# B293B_PIC32.net
KiCad netlist of a schematic drawn in Altium Designer
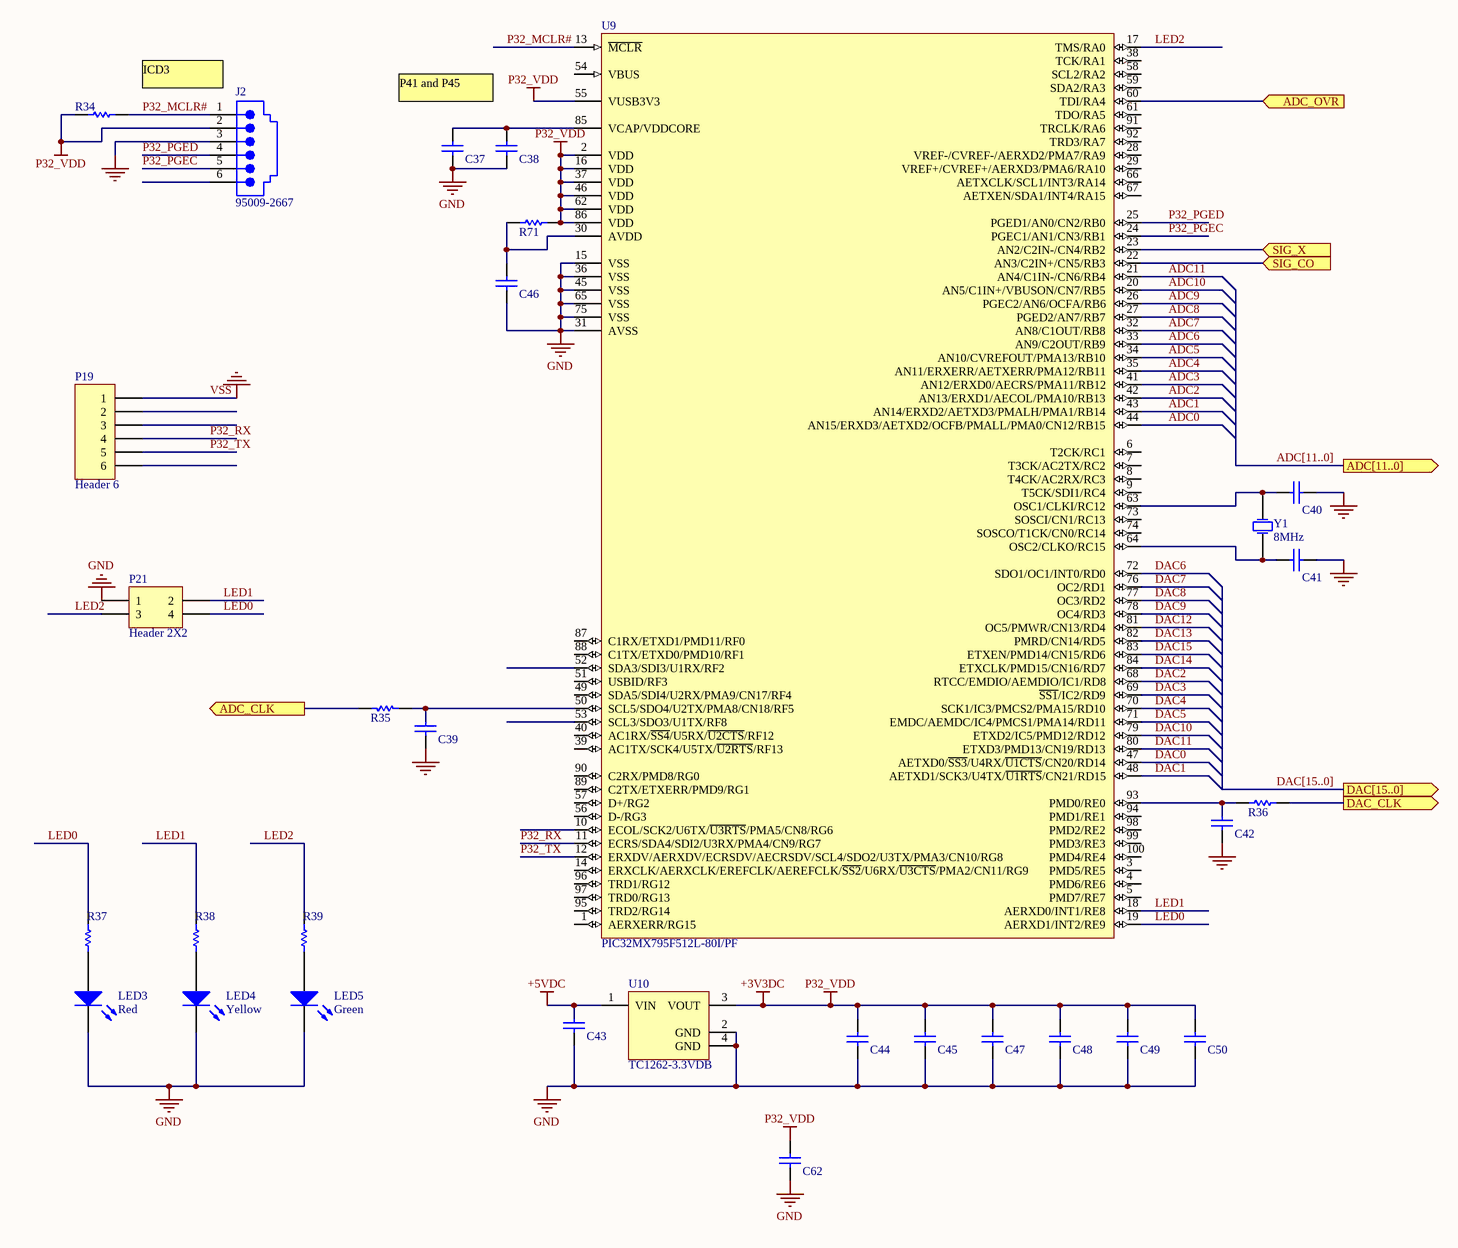
[diagram p0: B293B PIC32.SchDoc]

(export (version "E")
  (design (tool "Eeschema 10.0.6"))
  (components
    (comp (ref "C37")
      (value "CAP 10uF 25V 0805(2012)")
      (footprint "CAPC0805(2012)145_N")
      (description "CAP 10uF 25V ±20% 0805 (2012 Metric) Thickness 1.45mm SMD")
      (fields (field (name "TOLERANCE") "±20%"))
      (libsource (lib "Altium Content Vault") (part "CAP"))
    )
    (comp (ref "C38")
      (value "CAP 100nF 50V 1206(3216)")
      (footprint "CAPC1206(3216)170_L")
      (description "CAP 100nF 50V ±10% 1206 (3216 Metric) Thickness 1.7mm SMD")
      (fields (field (name "TOLERANCE") "±10%"))
      (libsource (lib "Altium Content Vault") (part "CAP"))
    )
    (comp (ref "C39")
      (value "CAP 1uF 25V 0805(2012)")
      (footprint "CAPC0805(2012)100_N")
      (description "CAP 1uF 25V ±20% 0805 (2012 Metric) Thickness 1mm SMD")
      (fields (field (name "TOLERANCE") "±20%"))
      (libsource (lib "Altium Content Vault") (part "CAP"))
    )
    (comp (ref "C40")
      (value "CAP 15pF 50V 0805(2012)")
      (footprint "CAPC0805(2012)75_L")
      (description "CAP 15pF 50V ±10% 0805 (2012 Metric) Thickness 0.75mm SMD")
      (fields (field (name "TOLERANCE") "±10%"))
      (libsource (lib "Altium Content Vault") (part "CAP"))
    )
    (comp (ref "C41")
      (value "CAP 15pF 50V 0805(2012)")
      (footprint "CAPC0805(2012)75_L")
      (description "CAP 15pF 50V ±10% 0805 (2012 Metric) Thickness 0.75mm SMD")
      (fields (field (name "TOLERANCE") "±10%"))
      (libsource (lib "Altium Content Vault") (part "CAP"))
    )
    (comp (ref "C42")
      (value "CAP 1uF 25V 0805(2012)")
      (footprint "CAPC0805(2012)100_N")
      (description "CAP 1uF 25V ±20% 0805 (2012 Metric) Thickness 1mm SMD")
      (fields (field (name "TOLERANCE") "±20%"))
      (libsource (lib "Altium Content Vault") (part "CAP"))
    )
    (comp (ref "C43")
      (value "CAP 10uF 25V 0805(2012)")
      (footprint "CAPC0805(2012)145_N")
      (description "CAP 10uF 25V ±20% 0805 (2012 Metric) Thickness 1.45mm SMD")
      (fields (field (name "TOLERANCE") "±20%"))
      (libsource (lib "Altium Content Vault") (part "CAP"))
    )
    (comp (ref "C44")
      (value "CAP 100nF 50V 0603(1608)")
      (footprint "CAPC0603(1608)100_N")
      (description "CAP 100nF 50V ±10% 0603 (1608 Metric) Thickness 1mm SMD")
      (fields (field (name "TOLERANCE") "±10%"))
      (libsource (lib "Altium Content Vault") (part "CAP"))
    )
    (comp (ref "C45")
      (value "CAP 100nF 50V 0603(1608)")
      (footprint "CAPC0603(1608)100_N")
      (description "CAP 100nF 50V ±10% 0603 (1608 Metric) Thickness 1mm SMD")
      (fields (field (name "TOLERANCE") "±10%"))
      (libsource (lib "Altium Content Vault") (part "CAP"))
    )
    (comp (ref "C46")
      (value "CAP 100nF 50V 0603(1608)")
      (footprint "CAPC0603(1608)100_N")
      (description "CAP 100nF 50V ±10% 0603 (1608 Metric) Thickness 1mm SMD")
      (fields (field (name "TOLERANCE") "±10%"))
      (libsource (lib "Altium Content Vault") (part "CAP"))
    )
    (comp (ref "C47")
      (value "CAP 100nF 50V 0603(1608)")
      (footprint "CAPC0603(1608)100_N")
      (description "CAP 100nF 50V ±10% 0603 (1608 Metric) Thickness 1mm SMD")
      (fields (field (name "TOLERANCE") "±10%"))
      (libsource (lib "Altium Content Vault") (part "CAP"))
    )
    (comp (ref "C48")
      (value "CAP 100nF 50V 0603(1608)")
      (footprint "CAPC0603(1608)100_N")
      (description "CAP 100nF 50V ±10% 0603 (1608 Metric) Thickness 1mm SMD")
      (fields (field (name "TOLERANCE") "±10%"))
      (libsource (lib "Altium Content Vault") (part "CAP"))
    )
    (comp (ref "C49")
      (value "CAP 100nF 50V 0603(1608)")
      (footprint "CAPC0603(1608)100_N")
      (description "CAP 100nF 50V ±10% 0603 (1608 Metric) Thickness 1mm SMD")
      (fields (field (name "TOLERANCE") "±10%"))
      (libsource (lib "Altium Content Vault") (part "CAP"))
    )
    (comp (ref "C50")
      (value "CAP 100nF 50V 0603(1608)")
      (footprint "CAPC0603(1608)100_N")
      (description "CAP 100nF 50V ±10% 0603 (1608 Metric) Thickness 1mm SMD")
      (fields (field (name "TOLERANCE") "±10%"))
      (libsource (lib "Altium Content Vault") (part "CAP"))
    )
    (comp (ref "C62")
      (value "CAP 47uF 25V 2220(5750)")
      (footprint "CAPC2220(5750)230_N")
      (description "CAP 47uF 25V -20% to +80% 2220 (5750 Metric) Thickness 2.2mm SMD")
      (fields (field (name "TOLERANCE") "-20% to +80%"))
      (libsource (lib "Altium Content Vault") (part "CAP"))
    )
    (comp (ref "J2")
      (value "95009-2667")
      (footprint "95009-2667")
      (description "Right Angle, Standard Profile, Flush Mount PCB Jack")
      (fields (field (name "PUBLISHER") "Altium Limited"))
      (libsource (lib "Matt SCH Library") (part "95009-2667"))
    )
    (comp (ref "LED3")
      (value "Red")
      (footprint "Matt PCB Library:1206 - LED")
      (description "LED, ALINGAP, SMD, 1206, RED")
      (fields (field (name "MANUFACTURER PART NUMBER") "KPC-3216SURCK"))
      (libsource (lib "Matt SCH Library") (part "LED 1206 RED"))
    )
    (comp (ref "LED4")
      (value "Yellow")
      (footprint "Matt PCB Library:1206 - LED")
      (description "LED, ALINGAP, SMD, 1206, YELLOW")
      (fields (field (name "MANUFACTURER PART NUMBER") "KPC-3216SYCK"))
      (libsource (lib "Matt SCH Library") (part "LED 1206 YELLOW"))
    )
    (comp (ref "LED5")
      (value "Green")
      (footprint "Matt PCB Library:1206 - LED")
      (description "LED, SMD, 1206, CLR LENS, GREEN")
      (fields (field (name "MANUFACTURER PART NUMBER") "KPC-3216SGC"))
      (libsource (lib "Matt SCH Library") (part "LED 1206 GREEN"))
    )
    (comp (ref "P19")
      (value "Header 6")
      (footprint "HDR1X6")
      (description "Header, 6-Pin")
      (fields (field (name "PUBLISHER") "Altium Limited"))
      (libsource (lib "Miscellaneous Connectors") (part "Header 6"))
    )
    (comp (ref "P21")
      (value "Header 2X2")
      (footprint "HDR2X2")
      (description "Header, 2-Pin, Dual row")
      (fields (field (name "PUBLISHER") "Altium Limited"))
      (libsource (lib "Miscellaneous Connectors") (part "Header 2X2"))
    )
    (comp (ref "R34")
      (value "10K 5% 0805(2012)")
      (footprint "RESC0805(2012)_L")
      (description "10K 0.125W 5% 0805 (2012 Metric)  SMD")
      (fields (field (name "POWER") "0.125 W") (field (name "TOLERANCE") "5 %"))
      (libsource (lib "Altium Content Vault") (part "RES"))
    )
    (comp (ref "R35")
      (value "10R 5% 0805(2012)")
      (footprint "RESC0805(2012)_L")
      (description "10R 0.125W 5% 0805 (2012 Metric)  SMD")
      (fields (field (name "TOLERANCE") "5 %") (field (name "POWER") "0.125 W"))
      (libsource (lib "Altium Content Vault") (part "RES"))
    )
    (comp (ref "R36")
      (value "220R 5% 0805(2012)")
      (footprint "RESC0805(2012)_L")
      (description "220R 0.125W 5% 0805 (2012 Metric)  SMD")
      (fields (field (name "TOLERANCE") "5 %") (field (name "POWER") "0.125 W"))
      (libsource (lib "Altium Content Vault") (part "RES"))
    )
    (comp (ref "R37")
      (value "1K 5% 0805(2012)")
      (footprint "RESC0805(2012)_N")
      (description "1K 0.125W 5% 0805 (2012 Metric)  SMD")
      (fields (field (name "TOLERANCE") "5 %") (field (name "POWER") "0.125 W"))
      (libsource (lib "Altium Content Vault") (part "RES"))
    )
    (comp (ref "R38")
      (value "1K 5% 0805(2012)")
      (footprint "RESC0805(2012)_N")
      (description "1K 0.125W 5% 0805 (2012 Metric)  SMD")
      (fields (field (name "TOLERANCE") "5 %") (field (name "POWER") "0.125 W"))
      (libsource (lib "Altium Content Vault") (part "RES"))
    )
    (comp (ref "R39")
      (value "1K 5% 0805(2012)")
      (footprint "RESC0805(2012)_N")
      (description "1K 0.125W 5% 0805 (2012 Metric)  SMD")
      (fields (field (name "TOLERANCE") "5 %") (field (name "POWER") "0.125 W"))
      (libsource (lib "Altium Content Vault") (part "RES"))
    )
    (comp (ref "R71")
      (value "10R 1% 0805(2012)")
      (footprint "RESC0805(2012)_M")
      (description "10R 0.125W 1% 0805 (2012 Metric)  SMD")
      (fields (field (name "TOLERANCE") "1 %") (field (name "POWER") "0.125 W"))
      (libsource (lib "Altium Content Vault") (part "RES"))
    )
    (comp (ref "U9")
      (value "PIC32MX795F512L-80I/PF")
      (footprint "TQFP-PF100_L")
      (libsource (lib "Altium Content Vault") (part "CMP-0048-00315-1"))
    )
    (comp (ref "U10")
      (value "TC1262-3.3VDB")
      (footprint "SOT-223-DB3_L")
      (description "500mA Fixed Output CMOS LDO, 3-Pin SOT-223, Extended Temperature")
      (libsource (lib "Altium Content Vault") (part "PM-LINEREG-TC1262-IL4"))
    )
    (comp (ref "Y1")
      (value "8MHz")
      (footprint "CRYSTAL_HC49-US-SM")
      (description "CRYSTAL, 8MHZ, 16PF, SMD")
      (fields (field (name "MANUFACTURER PART NUMBER") "HC49SM-8-30-50-60-16-ATF"))
      (libsource (lib "Matt SCH Library") (part "SMD Crystal 8HMz HC-49"))
    )
  )
  (nets
    (net (code "1") (name "+3V3DC") (class "Default")
      (node (ref "C44") (pin "1") (pinfunction "1_1") (pintype "passive"))
      (node (ref "C45") (pin "1") (pinfunction "1_1") (pintype "passive"))
      (node (ref "C47") (pin "1") (pinfunction "1_1") (pintype "passive"))
      (node (ref "C48") (pin "1") (pinfunction "1_1") (pintype "passive"))
      (node (ref "C49") (pin "1") (pinfunction "1_1") (pintype "passive"))
      (node (ref "C50") (pin "1") (pinfunction "1_1") (pintype "passive"))
      (node (ref "C62") (pin "2") (pinfunction "2_2") (pintype "passive"))
      (node (ref "J2") (pin "2") (pinfunction "2_2") (pintype "passive"))
      (node (ref "R34") (pin "1") (pinfunction "1_1") (pintype "passive"))
      (node (ref "R71") (pin "2") (pinfunction "2_2") (pintype "passive"))
      (node (ref "U10") (pin "3") (pinfunction "VOUT_3") (pintype "power_in"))
      (node (ref "U9") (pin "16") (pinfunction "VDD_16") (pintype "power_in"))
      (node (ref "U9") (pin "2") (pinfunction "VDD_2") (pintype "power_in"))
      (node (ref "U9") (pin "37") (pinfunction "VDD_37") (pintype "power_in"))
      (node (ref "U9") (pin "46") (pinfunction "VDD_46") (pintype "power_in"))
      (node (ref "U9") (pin "55") (pinfunction "VUSB3V3_55") (pintype "power_in"))
      (node (ref "U9") (pin "62") (pinfunction "VDD_62") (pintype "power_in"))
      (node (ref "U9") (pin "86") (pinfunction "VDD_86") (pintype "power_in"))
    )
    (net (code "2") (name "+5VDC") (class "Default")
      (node (ref "C43") (pin "1") (pinfunction "1_1") (pintype "passive"))
      (node (ref "U10") (pin "1") (pinfunction "VIN_1") (pintype "power_in"))
    )
    (net (code "3") (name "/ADC0") (class "Default")
      (node (ref "U9") (pin "44") (pinfunction "AN15/ERXD3/AETXD2/OCFB/PMALL/PMA0/CN12/RB15_44") (pintype "bidirectional"))
    )
    (net (code "4") (name "/ADC1") (class "Default")
      (node (ref "U9") (pin "43") (pinfunction "AN14/ERXD2/AETXD3/PMALH/PMA1/RB14_43") (pintype "bidirectional"))
    )
    (net (code "5") (name "/ADC2") (class "Default")
      (node (ref "U9") (pin "42") (pinfunction "AN13/ERXD1/AECOL/PMA10/RB13_42") (pintype "bidirectional"))
    )
    (net (code "6") (name "/ADC3") (class "Default")
      (node (ref "U9") (pin "41") (pinfunction "AN12/ERXD0/AECRS/PMA11/RB12_41") (pintype "bidirectional"))
    )
    (net (code "7") (name "/ADC4") (class "Default")
      (node (ref "U9") (pin "35") (pinfunction "AN11/ERXERR/AETXERR/PMA12/RB11_35") (pintype "bidirectional"))
    )
    (net (code "8") (name "/ADC5") (class "Default")
      (node (ref "U9") (pin "34") (pinfunction "AN10/CVREFOUT/PMA13/RB10_34") (pintype "bidirectional"))
    )
    (net (code "9") (name "/ADC6") (class "Default")
      (node (ref "U9") (pin "33") (pinfunction "AN9/C2OUT/RB9_33") (pintype "bidirectional"))
    )
    (net (code "10") (name "/ADC7") (class "Default")
      (node (ref "U9") (pin "32") (pinfunction "AN8/C1OUT/RB8_32") (pintype "bidirectional"))
    )
    (net (code "11") (name "/ADC8") (class "Default")
      (node (ref "U9") (pin "27") (pinfunction "PGED2/AN7/RB7_27") (pintype "bidirectional"))
    )
    (net (code "12") (name "/ADC9") (class "Default")
      (node (ref "U9") (pin "26") (pinfunction "PGEC2/AN6/OCFA/RB6_26") (pintype "bidirectional"))
    )
    (net (code "13") (name "/ADC10") (class "Default")
      (node (ref "U9") (pin "20") (pinfunction "AN5/C1IN+/VBUSON/CN7/RB5_20") (pintype "bidirectional"))
    )
    (net (code "14") (name "/ADC11") (class "Default")
      (node (ref "U9") (pin "21") (pinfunction "AN4/C1IN-/CN6/RB4_21") (pintype "bidirectional"))
    )
    (net (code "16") (name "/ADC_CLK") (class "Default")
      (node (ref "R35") (pin "2") (pinfunction "2_2") (pintype "passive"))
    )
    (net (code "17") (name "/ADC_OVR") (class "Default")
      (node (ref "U9") (pin "60") (pinfunction "TDI/RA4_60") (pintype "bidirectional"))
    )
    (net (code "18") (name "/DAC0") (class "Default")
      (node (ref "U9") (pin "47") (pinfunction "AETXD0/~{SS3}/U4RX/~{U1CTS}/CN20/RD14_47") (pintype "bidirectional"))
    )
    (net (code "19") (name "/DAC1") (class "Default")
      (node (ref "U9") (pin "48") (pinfunction "AETXD1/SCK3/U4TX/~{U1RTS}/CN21/RD15_48") (pintype "bidirectional"))
    )
    (net (code "20") (name "/DAC2") (class "Default")
      (node (ref "U9") (pin "68") (pinfunction "RTCC/EMDIO/AEMDIO/IC1/RD8_68") (pintype "bidirectional"))
    )
    (net (code "21") (name "/DAC3") (class "Default")
      (node (ref "U9") (pin "69") (pinfunction "~{SS1}/IC2/RD9_69") (pintype "bidirectional"))
    )
    (net (code "22") (name "/DAC4") (class "Default")
      (node (ref "U9") (pin "70") (pinfunction "SCK1/IC3/PMCS2/PMA15/RD10_70") (pintype "bidirectional"))
    )
    (net (code "23") (name "/DAC5") (class "Default")
      (node (ref "U9") (pin "71") (pinfunction "EMDC/AEMDC/IC4/PMCS1/PMA14/RD11_71") (pintype "bidirectional"))
    )
    (net (code "24") (name "/DAC6") (class "Default")
      (node (ref "U9") (pin "72") (pinfunction "SDO1/OC1/INT0/RD0_72") (pintype "bidirectional"))
    )
    (net (code "25") (name "/DAC7") (class "Default")
      (node (ref "U9") (pin "76") (pinfunction "OC2/RD1_76") (pintype "bidirectional"))
    )
    (net (code "26") (name "/DAC8") (class "Default")
      (node (ref "U9") (pin "77") (pinfunction "OC3/RD2_77") (pintype "bidirectional"))
    )
    (net (code "27") (name "/DAC9") (class "Default")
      (node (ref "U9") (pin "78") (pinfunction "OC4/RD3_78") (pintype "bidirectional"))
    )
    (net (code "28") (name "/DAC10") (class "Default")
      (node (ref "U9") (pin "79") (pinfunction "ETXD2/IC5/PMD12/RD12_79") (pintype "bidirectional"))
    )
    (net (code "29") (name "/DAC11") (class "Default")
      (node (ref "U9") (pin "80") (pinfunction "ETXD3/PMD13/CN19/RD13_80") (pintype "bidirectional"))
    )
    (net (code "30") (name "/DAC12") (class "Default")
      (node (ref "U9") (pin "81") (pinfunction "OC5/PMWR/CN13/RD4_81") (pintype "bidirectional"))
    )
    (net (code "31") (name "/DAC13") (class "Default")
      (node (ref "U9") (pin "82") (pinfunction "PMRD/CN14/RD5_82") (pintype "bidirectional"))
    )
    (net (code "32") (name "/DAC14") (class "Default")
      (node (ref "U9") (pin "84") (pinfunction "ETXCLK/PMD15/CN16/RD7_84") (pintype "bidirectional"))
    )
    (net (code "33") (name "/DAC15") (class "Default")
      (node (ref "U9") (pin "83") (pinfunction "ETXEN/PMD14/CN15/RD6_83") (pintype "bidirectional"))
    )
    (net (code "35") (name "/DAC_CLK") (class "Default")
      (node (ref "R36") (pin "2") (pinfunction "2_2") (pintype "passive"))
    )
    (net (code "36") (name "/LED0") (class "Default")
      (node (ref "P21") (pin "4") (pinfunction "4_4") (pintype "passive"))
      (node (ref "R37") (pin "2") (pinfunction "2_2") (pintype "passive"))
      (node (ref "U9") (pin "19") (pinfunction "AERXD1/INT2/RE9_19") (pintype "bidirectional"))
    )
    (net (code "37") (name "/LED1") (class "Default")
      (node (ref "P21") (pin "2") (pinfunction "2_2") (pintype "passive"))
      (node (ref "R38") (pin "2") (pinfunction "2_2") (pintype "passive"))
      (node (ref "U9") (pin "18") (pinfunction "AERXD0/INT1/RE8_18") (pintype "bidirectional"))
    )
    (net (code "38") (name "/LED2") (class "Default")
      (node (ref "P21") (pin "3") (pinfunction "3_3") (pintype "passive"))
      (node (ref "R39") (pin "2") (pinfunction "2_2") (pintype "passive"))
      (node (ref "U9") (pin "17") (pinfunction "TMS/RA0_17") (pintype "bidirectional"))
    )
    (net (code "39") (name "/P32_MCLR#") (class "Default")
      (node (ref "J2") (pin "1") (pinfunction "1_1") (pintype "passive"))
      (node (ref "R34") (pin "2") (pinfunction "2_2") (pintype "passive"))
      (node (ref "U9") (pin "13") (pinfunction "~{MCLR}_13") (pintype "input"))
    )
    (net (code "40") (name "/P32_PGEC") (class "Default")
      (node (ref "J2") (pin "5") (pinfunction "5_5") (pintype "passive"))
      (node (ref "U9") (pin "24") (pinfunction "PGEC1/AN1/CN3/RB1_24") (pintype "bidirectional"))
    )
    (net (code "41") (name "/P32_PGED") (class "Default")
      (node (ref "J2") (pin "4") (pinfunction "4_4") (pintype "passive"))
      (node (ref "U9") (pin "25") (pinfunction "PGED1/AN0/CN2/RB0_25") (pintype "bidirectional"))
    )
    (net (code "42") (name "/P32_RX") (class "Default")
      (node (ref "P19") (pin "4") (pinfunction "4_4") (pintype "passive"))
      (node (ref "U9") (pin "11") (pinfunction "ECRS/SDA4/SDI2/U3RX/PMA4/CN9/RG7_11") (pintype "bidirectional"))
    )
    (net (code "43") (name "/P32_TX") (class "Default")
      (node (ref "P19") (pin "5") (pinfunction "5_5") (pintype "passive"))
      (node (ref "U9") (pin "12") (pinfunction "ERXDV/AERXDV/ECRSDV/AECRSDV/SCL4/SDO2/U3TX/PMA3/CN10/RG8_12") (pintype "bidirectional"))
    )
    (net (code "44") (name "/SIG_CO") (class "Default")
      (node (ref "U9") (pin "22") (pinfunction "AN3/C2IN+/CN5/RB3_22") (pintype "bidirectional"))
    )
    (net (code "45") (name "/SIG_X") (class "Default")
      (node (ref "U9") (pin "23") (pinfunction "AN2/C2IN-/CN4/RB2_23") (pintype "bidirectional"))
    )
    (net (code "46") (name "GND") (class "Default")
      (node (ref "C37") (pin "2") (pinfunction "2_2") (pintype "passive"))
      (node (ref "C38") (pin "2") (pinfunction "2_2") (pintype "passive"))
      (node (ref "C39") (pin "2") (pinfunction "2_2") (pintype "passive"))
      (node (ref "C40") (pin "1") (pinfunction "1_1") (pintype "passive"))
      (node (ref "C41") (pin "1") (pinfunction "1_1") (pintype "passive"))
      (node (ref "C42") (pin "2") (pinfunction "2_2") (pintype "passive"))
      (node (ref "C43") (pin "2") (pinfunction "2_2") (pintype "passive"))
      (node (ref "C44") (pin "2") (pinfunction "2_2") (pintype "passive"))
      (node (ref "C45") (pin "2") (pinfunction "2_2") (pintype "passive"))
      (node (ref "C46") (pin "2") (pinfunction "2_2") (pintype "passive"))
      (node (ref "C47") (pin "2") (pinfunction "2_2") (pintype "passive"))
      (node (ref "C48") (pin "2") (pinfunction "2_2") (pintype "passive"))
      (node (ref "C49") (pin "2") (pinfunction "2_2") (pintype "passive"))
      (node (ref "C50") (pin "2") (pinfunction "2_2") (pintype "passive"))
      (node (ref "C62") (pin "1") (pinfunction "1_1") (pintype "passive"))
      (node (ref "J2") (pin "3") (pinfunction "3_3") (pintype "passive"))
      (node (ref "LED3") (pin "K") (pinfunction "K_K") (pintype "passive"))
      (node (ref "LED4") (pin "K") (pinfunction "K_K") (pintype "passive"))
      (node (ref "LED5") (pin "K") (pinfunction "K_K") (pintype "passive"))
      (node (ref "P19") (pin "1") (pinfunction "1_1") (pintype "passive"))
      (node (ref "P21") (pin "1") (pinfunction "1_1") (pintype "passive"))
      (node (ref "U10") (pin "2") (pinfunction "GND_2") (pintype "power_in"))
      (node (ref "U10") (pin "4") (pinfunction "GND_4") (pintype "power_in"))
      (node (ref "U9") (pin "15") (pinfunction "VSS_15") (pintype "power_in"))
      (node (ref "U9") (pin "31") (pinfunction "AVSS_31") (pintype "power_in"))
      (node (ref "U9") (pin "36") (pinfunction "VSS_36") (pintype "power_in"))
      (node (ref "U9") (pin "45") (pinfunction "VSS_45") (pintype "power_in"))
      (node (ref "U9") (pin "65") (pinfunction "VSS_65") (pintype "power_in"))
      (node (ref "U9") (pin "75") (pinfunction "VSS_75") (pintype "power_in"))
    )
    (net (code "47") (name "Net-(LED3-PadA)") (class "Default")
      (node (ref "LED3") (pin "A") (pinfunction "A_A") (pintype "passive"))
      (node (ref "R37") (pin "1") (pinfunction "1_1") (pintype "passive"))
    )
    (net (code "48") (name "Net-(LED4-PadA)") (class "Default")
      (node (ref "LED4") (pin "A") (pinfunction "A_A") (pintype "passive"))
      (node (ref "R38") (pin "1") (pinfunction "1_1") (pintype "passive"))
    )
    (net (code "49") (name "Net-(LED5-PadA)") (class "Default")
      (node (ref "LED5") (pin "A") (pinfunction "A_A") (pintype "passive"))
      (node (ref "R39") (pin "1") (pinfunction "1_1") (pintype "passive"))
    )
    (net (code "50") (name "Net-(U9-AVDD)") (class "Default")
      (node (ref "C46") (pin "1") (pinfunction "1_1") (pintype "passive"))
      (node (ref "R71") (pin "1") (pinfunction "1_1") (pintype "passive"))
      (node (ref "U9") (pin "30") (pinfunction "AVDD_30") (pintype "power_in"))
    )
    (net (code "51") (name "Net-(U9-OSC1{slash}CLKI{slash}RC12)") (class "Default")
      (node (ref "C40") (pin "2") (pinfunction "2_2") (pintype "passive"))
      (node (ref "U9") (pin "63") (pinfunction "OSC1/CLKI/RC12_63") (pintype "bidirectional"))
      (node (ref "Y1") (pin "1") (pinfunction "OSC1_1") (pintype "passive"))
    )
    (net (code "52") (name "Net-(U9-OSC2{slash}CLKO{slash}RC15)") (class "Default")
      (node (ref "C41") (pin "2") (pinfunction "2_2") (pintype "passive"))
      (node (ref "U9") (pin "64") (pinfunction "OSC2/CLKO/RC15_64") (pintype "bidirectional"))
      (node (ref "Y1") (pin "2") (pinfunction "OSC2_2") (pintype "passive"))
    )
    (net (code "53") (name "Net-(U9-PMD0{slash}RE0)") (class "Default")
      (node (ref "C42") (pin "1") (pinfunction "1_1") (pintype "passive"))
      (node (ref "R36") (pin "1") (pinfunction "1_1") (pintype "passive"))
      (node (ref "U9") (pin "93") (pinfunction "PMD0/RE0_93") (pintype "bidirectional"))
    )
    (net (code "54") (name "Net-(U9-SCL5{slash}SDO4{slash}U2TX{slash}PMA8{slash}CN18{slash}RF5)") (class "Default")
      (node (ref "C39") (pin "1") (pinfunction "1_1") (pintype "passive"))
      (node (ref "R35") (pin "1") (pinfunction "1_1") (pintype "passive"))
      (node (ref "U9") (pin "50") (pinfunction "SCL5/SDO4/U2TX/PMA8/CN18/RF5_50") (pintype "bidirectional"))
    )
    (net (code "55") (name "Net-(U9-VCAP{slash}VDDCORE)") (class "Default")
      (node (ref "C37") (pin "1") (pinfunction "1_1") (pintype "passive"))
      (node (ref "C38") (pin "1") (pinfunction "1_1") (pintype "passive"))
      (node (ref "U9") (pin "85") (pinfunction "VCAP/VDDCORE_85") (pintype "power_in"))
    )
    (net (code "56") (name "unconnected-(J2-Pad6)") (class "Default")
      (node (ref "J2") (pin "6") (pinfunction "6_6") (pintype "passive"))
    )
    (net (code "57") (name "unconnected-(P19-Pad2)") (class "Default")
      (node (ref "P19") (pin "2") (pinfunction "2_2") (pintype "passive"))
    )
    (net (code "58") (name "unconnected-(P19-Pad3)") (class "Default")
      (node (ref "P19") (pin "3") (pinfunction "3_3") (pintype "passive"))
    )
    (net (code "59") (name "unconnected-(P19-Pad6)") (class "Default")
      (node (ref "P19") (pin "6") (pinfunction "6_6") (pintype "passive"))
    )
    (net (code "60") (name "unconnected-(U9-AC1RX{slash}~{SS4}{slash}U5RX{slash}~{U2CTS}{slash}RF12-Pad40)") (class "Default")
      (node (ref "U9") (pin "40") (pinfunction "AC1RX/~{SS4}/U5RX/~{U2CTS}/RF12_40") (pintype "bidirectional"))
    )
    (net (code "61") (name "unconnected-(U9-AC1TX{slash}SCK4{slash}U5TX{slash}~{U2RTS}{slash}RF13-Pad39)") (class "Default")
      (node (ref "U9") (pin "39") (pinfunction "AC1TX/SCK4/U5TX/~{U2RTS}/RF13_39") (pintype "bidirectional"))
    )
    (net (code "62") (name "unconnected-(U9-AERXERR{slash}RG15-Pad1)") (class "Default")
      (node (ref "U9") (pin "1") (pinfunction "AERXERR/RG15_1") (pintype "bidirectional"))
    )
    (net (code "63") (name "unconnected-(U9-AETXCLK{slash}SCL1{slash}INT3{slash}RA14-Pad66)") (class "Default")
      (node (ref "U9") (pin "66") (pinfunction "AETXCLK/SCL1/INT3/RA14_66") (pintype "bidirectional"))
    )
    (net (code "64") (name "unconnected-(U9-AETXEN{slash}SDA1{slash}INT4{slash}RA15-Pad67)") (class "Default")
      (node (ref "U9") (pin "67") (pinfunction "AETXEN/SDA1/INT4/RA15_67") (pintype "bidirectional"))
    )
    (net (code "65") (name "unconnected-(U9-C1RX{slash}ETXD1{slash}PMD11{slash}RF0-Pad87)") (class "Default")
      (node (ref "U9") (pin "87") (pinfunction "C1RX/ETXD1/PMD11/RF0_87") (pintype "bidirectional"))
    )
    (net (code "66") (name "unconnected-(U9-C1TX{slash}ETXD0{slash}PMD10{slash}RF1-Pad88)") (class "Default")
      (node (ref "U9") (pin "88") (pinfunction "C1TX/ETXD0/PMD10/RF1_88") (pintype "bidirectional"))
    )
    (net (code "67") (name "unconnected-(U9-C2RX{slash}PMD8{slash}RG0-Pad90)") (class "Default")
      (node (ref "U9") (pin "90") (pinfunction "C2RX/PMD8/RG0_90") (pintype "bidirectional"))
    )
    (net (code "68") (name "unconnected-(U9-C2TX{slash}ETXERR{slash}PMD9{slash}RG1-Pad89)") (class "Default")
      (node (ref "U9") (pin "89") (pinfunction "C2TX/ETXERR/PMD9/RG1_89") (pintype "bidirectional"))
    )
    (net (code "69") (name "unconnected-(U9-D+{slash}RG2-Pad57)") (class "Default")
      (node (ref "U9") (pin "57") (pinfunction "D+/RG2_57") (pintype "bidirectional"))
    )
    (net (code "70") (name "unconnected-(U9-D-{slash}RG3-Pad56)") (class "Default")
      (node (ref "U9") (pin "56") (pinfunction "D-/RG3_56") (pintype "bidirectional"))
    )
    (net (code "71") (name "unconnected-(U9-ECOL{slash}SCK2{slash}U6TX{slash}~{U3RTS}{slash}PMA5{slash}CN8{slash}RG6-Pad10)") (class "Default")
      (node (ref "U9") (pin "10") (pinfunction "ECOL/SCK2/U6TX/~{U3RTS}/PMA5/CN8/RG6_10") (pintype "bidirectional"))
    )
    (net (code "72") (name "unconnected-(U9-ERXCLK{slash}AERXCLK{slash}EREFCLK{slash}AEREFCLK{slash}~{SS2}{slash}U6RX{slash}~{U3CTS}{slash}PMA2{slash}CN11{slash}RG9-Pad14)") (class "Default")
      (node (ref "U9") (pin "14") (pinfunction "ERXCLK/AERXCLK/EREFCLK/AEREFCLK/~{SS2}/U6RX/~{U3CTS}/PMA2/CN11/RG9_14") (pintype "bidirectional"))
    )
    (net (code "73") (name "unconnected-(U9-PMD1{slash}RE1-Pad94)") (class "Default")
      (node (ref "U9") (pin "94") (pinfunction "PMD1/RE1_94") (pintype "bidirectional"))
    )
    (net (code "74") (name "unconnected-(U9-PMD2{slash}RE2-Pad98)") (class "Default")
      (node (ref "U9") (pin "98") (pinfunction "PMD2/RE2_98") (pintype "bidirectional"))
    )
    (net (code "75") (name "unconnected-(U9-PMD3{slash}RE3-Pad99)") (class "Default")
      (node (ref "U9") (pin "99") (pinfunction "PMD3/RE3_99") (pintype "bidirectional"))
    )
    (net (code "76") (name "unconnected-(U9-PMD4{slash}RE4-Pad100)") (class "Default")
      (node (ref "U9") (pin "100") (pinfunction "PMD4/RE4_100") (pintype "bidirectional"))
    )
    (net (code "77") (name "unconnected-(U9-PMD5{slash}RE5-Pad3)") (class "Default")
      (node (ref "U9") (pin "3") (pinfunction "PMD5/RE5_3") (pintype "bidirectional"))
    )
    (net (code "78") (name "unconnected-(U9-PMD6{slash}RE6-Pad4)") (class "Default")
      (node (ref "U9") (pin "4") (pinfunction "PMD6/RE6_4") (pintype "bidirectional"))
    )
    (net (code "79") (name "unconnected-(U9-PMD7{slash}RE7-Pad5)") (class "Default")
      (node (ref "U9") (pin "5") (pinfunction "PMD7/RE7_5") (pintype "bidirectional"))
    )
    (net (code "80") (name "unconnected-(U9-SCL2{slash}RA2-Pad58)") (class "Default")
      (node (ref "U9") (pin "58") (pinfunction "SCL2/RA2_58") (pintype "bidirectional"))
    )
    (net (code "81") (name "unconnected-(U9-SCL3{slash}SDO3{slash}U1TX{slash}RF8-Pad53)") (class "Default")
      (node (ref "U9") (pin "53") (pinfunction "SCL3/SDO3/U1TX/RF8_53") (pintype "bidirectional"))
    )
    (net (code "82") (name "unconnected-(U9-SDA2{slash}RA3-Pad59)") (class "Default")
      (node (ref "U9") (pin "59") (pinfunction "SDA2/RA3_59") (pintype "bidirectional"))
    )
    (net (code "83") (name "unconnected-(U9-SDA3{slash}SDI3{slash}U1RX{slash}RF2-Pad52)") (class "Default")
      (node (ref "U9") (pin "52") (pinfunction "SDA3/SDI3/U1RX/RF2_52") (pintype "bidirectional"))
    )
    (net (code "84") (name "unconnected-(U9-SDA5{slash}SDI4{slash}U2RX{slash}PMA9{slash}CN17{slash}RF4-Pad49)") (class "Default")
      (node (ref "U9") (pin "49") (pinfunction "SDA5/SDI4/U2RX/PMA9/CN17/RF4_49") (pintype "bidirectional"))
    )
    (net (code "85") (name "unconnected-(U9-SOSCI{slash}CN1{slash}RC13-Pad73)") (class "Default")
      (node (ref "U9") (pin "73") (pinfunction "SOSCI/CN1/RC13_73") (pintype "bidirectional"))
    )
    (net (code "86") (name "unconnected-(U9-SOSCO{slash}T1CK{slash}CN0{slash}RC14-Pad74)") (class "Default")
      (node (ref "U9") (pin "74") (pinfunction "SOSCO/T1CK/CN0/RC14_74") (pintype "bidirectional"))
    )
    (net (code "87") (name "unconnected-(U9-T2CK{slash}RC1-Pad6)") (class "Default")
      (node (ref "U9") (pin "6") (pinfunction "T2CK/RC1_6") (pintype "bidirectional"))
    )
    (net (code "88") (name "unconnected-(U9-T3CK{slash}AC2TX{slash}RC2-Pad7)") (class "Default")
      (node (ref "U9") (pin "7") (pinfunction "T3CK/AC2TX/RC2_7") (pintype "bidirectional"))
    )
    (net (code "89") (name "unconnected-(U9-T4CK{slash}AC2RX{slash}RC3-Pad8)") (class "Default")
      (node (ref "U9") (pin "8") (pinfunction "T4CK/AC2RX/RC3_8") (pintype "bidirectional"))
    )
    (net (code "90") (name "unconnected-(U9-T5CK{slash}SDI1{slash}RC4-Pad9)") (class "Default")
      (node (ref "U9") (pin "9") (pinfunction "T5CK/SDI1/RC4_9") (pintype "bidirectional"))
    )
    (net (code "91") (name "unconnected-(U9-TCK{slash}RA1-Pad38)") (class "Default")
      (node (ref "U9") (pin "38") (pinfunction "TCK/RA1_38") (pintype "bidirectional"))
    )
    (net (code "92") (name "unconnected-(U9-TDO{slash}RA5-Pad61)") (class "Default")
      (node (ref "U9") (pin "61") (pinfunction "TDO/RA5_61") (pintype "bidirectional"))
    )
    (net (code "93") (name "unconnected-(U9-TRCLK{slash}RA6-Pad91)") (class "Default")
      (node (ref "U9") (pin "91") (pinfunction "TRCLK/RA6_91") (pintype "bidirectional"))
    )
    (net (code "94") (name "unconnected-(U9-TRD0{slash}RG13-Pad97)") (class "Default")
      (node (ref "U9") (pin "97") (pinfunction "TRD0/RG13_97") (pintype "bidirectional"))
    )
    (net (code "95") (name "unconnected-(U9-TRD1{slash}RG12-Pad96)") (class "Default")
      (node (ref "U9") (pin "96") (pinfunction "TRD1/RG12_96") (pintype "bidirectional"))
    )
    (net (code "96") (name "unconnected-(U9-TRD2{slash}RG14-Pad95)") (class "Default")
      (node (ref "U9") (pin "95") (pinfunction "TRD2/RG14_95") (pintype "bidirectional"))
    )
    (net (code "97") (name "unconnected-(U9-TRD3{slash}RA7-Pad92)") (class "Default")
      (node (ref "U9") (pin "92") (pinfunction "TRD3/RA7_92") (pintype "bidirectional"))
    )
    (net (code "98") (name "unconnected-(U9-USBID{slash}RF3-Pad51)") (class "Default")
      (node (ref "U9") (pin "51") (pinfunction "USBID/RF3_51") (pintype "bidirectional"))
    )
    (net (code "99") (name "unconnected-(U9-VBUS-Pad54)") (class "Default")
      (node (ref "U9") (pin "54") (pinfunction "VBUS_54") (pintype "input"))
    )
    (net (code "100") (name "unconnected-(U9-VREF+{slash}CVREF+{slash}AERXD3{slash}PMA6{slash}RA10-Pad29)") (class "Default")
      (node (ref "U9") (pin "29") (pinfunction "VREF+/CVREF+/AERXD3/PMA6/RA10_29") (pintype "bidirectional"))
    )
    (net (code "101") (name "unconnected-(U9-VREF-{slash}CVREF-{slash}AERXD2{slash}PMA7{slash}RA9-Pad28)") (class "Default")
      (node (ref "U9") (pin "28") (pinfunction "VREF-/CVREF-/AERXD2/PMA7/RA9_28") (pintype "bidirectional"))
    )
  )
)
